# tusb_wiggler_-_b_conn.net
KiCad netlist of a schematic drawn in EAGLE
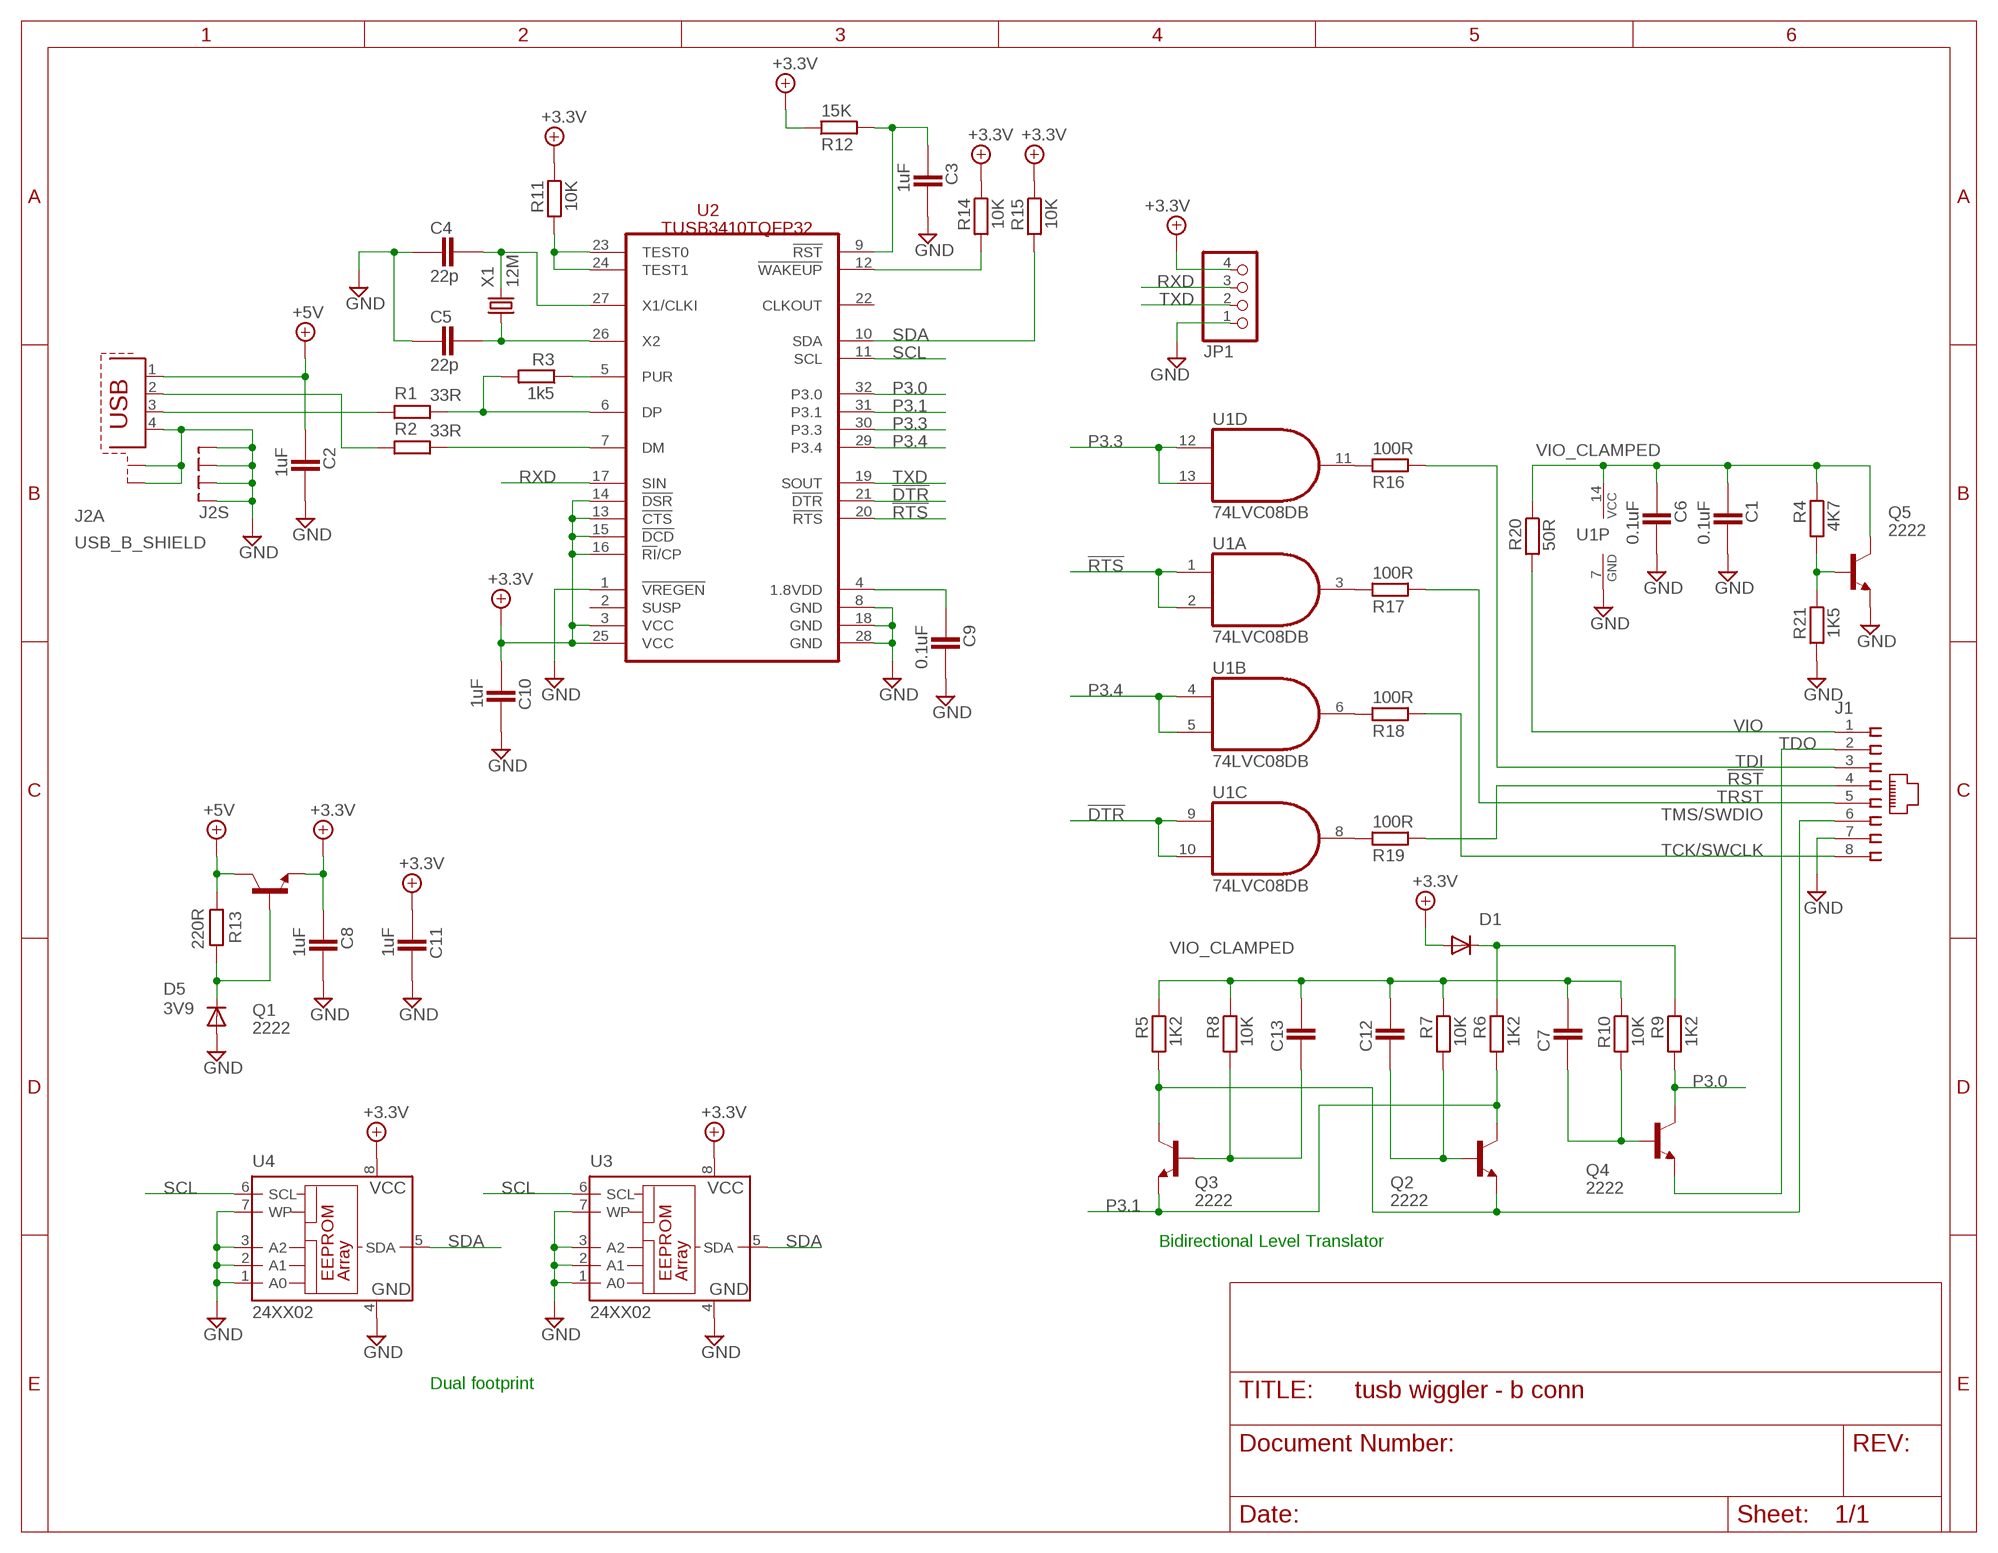
[diagram p0: schematic, sheet 1]

(export (version "E")
  (design (tool "Eeschema 10.0.6"))
  (components
    (comp (ref "C1")
      (value "0.1uF")
      (footprint "eagle-import:CAPC3215X168N")
      (libsource (lib "eagle-import") (part "CAPACITOR_1206"))
    )
    (comp (ref "C2")
      (value "1uF")
      (footprint "eagle-import:CAPC1608X92N")
      (libsource (lib "eagle-import") (part "CAPACITOR_0603"))
    )
    (comp (ref "C3")
      (value "1uF")
      (footprint "eagle-import:CAPC1608X92N")
      (libsource (lib "eagle-import") (part "CAPACITOR_0603"))
    )
    (comp (ref "C4")
      (value "22p")
      (footprint "eagle-import:CAP2012X70N")
      (libsource (lib "eagle-import") (part "CAPACITOR_0805N"))
    )
    (comp (ref "C5")
      (value "22p")
      (footprint "eagle-import:CAP2012X70N")
      (libsource (lib "eagle-import") (part "CAPACITOR_0805N"))
    )
    (comp (ref "C6")
      (value "0.1uF")
      (footprint "eagle-import:CAPC1608X92N")
      (libsource (lib "eagle-import") (part "CAPACITOR_0603"))
    )
    (comp (ref "C7")
      (value "CAPACITOR_0805N")
      (footprint "eagle-import:CAP2012X70N")
      (libsource (lib "eagle-import") (part "CAPACITOR_0805N"))
    )
    (comp (ref "C8")
      (value "1uF")
      (footprint "eagle-import:CAPC1608X92N")
      (libsource (lib "eagle-import") (part "CAPACITOR_0603"))
    )
    (comp (ref "C9")
      (value "0.1uF")
      (footprint "eagle-import:CAP2012X70N")
      (libsource (lib "eagle-import") (part "CAPACITOR_0805N"))
    )
    (comp (ref "C10")
      (value "1uF")
      (footprint "eagle-import:CAPC1608X92N")
      (libsource (lib "eagle-import") (part "CAPACITOR_0603"))
    )
    (comp (ref "C11")
      (value "1uF")
      (footprint "eagle-import:CAPC1608X92N")
      (libsource (lib "eagle-import") (part "CAPACITOR_0603"))
    )
    (comp (ref "C12")
      (value "CAPACITOR_0805N")
      (footprint "eagle-import:CAP2012X70N")
      (libsource (lib "eagle-import") (part "CAPACITOR_0805N"))
    )
    (comp (ref "C13")
      (value "CAPACITOR_0805N")
      (footprint "eagle-import:CAP2012X70N")
      (libsource (lib "eagle-import") (part "CAPACITOR_0805N"))
    )
    (comp (ref "D1")
      (value "DIODE-SOD110-W")
      (footprint "eagle-import:SOD110-W")
      (libsource (lib "eagle-import") (part "DIODE-SOD110-W"))
    )
    (comp (ref "D5")
      (value "3V9")
      (footprint "eagle-import:MELF-MLL41")
      (libsource (lib "eagle-import") (part "DIODE-MELF-MLL41"))
    )
    (comp (ref "J1")
      (value "520426-4")
      (footprint "eagle-import:520426-4")
      (libsource (lib "eagle-import") (part "520426-4"))
    )
    (comp (ref "J2")
      (value "USB_B_SHIELD")
      (footprint "eagle-import:PN61729-S")
      (libsource (lib "eagle-import") (part "USB_B_SHIELD"))
    )
    (comp (ref "JP1")
      (value "PINHD-1X4_2.54")
      (footprint "eagle-import:1X04")
      (libsource (lib "eagle-import") (part "PINHD-1X4_2.54"))
    )
    (comp (ref "Q1")
      (value "2222")
      (footprint "eagle-import:SOT95P280X135-3N")
      (libsource (lib "eagle-import") (part "NPN_SOT-23"))
    )
    (comp (ref "Q2")
      (value "2222")
      (footprint "eagle-import:SOT95P280X135-3N")
      (libsource (lib "eagle-import") (part "NPN_SOT-23"))
    )
    (comp (ref "Q3")
      (value "2222")
      (footprint "eagle-import:SOT95P280X135-3N")
      (libsource (lib "eagle-import") (part "NPN_SOT-23"))
    )
    (comp (ref "Q4")
      (value "2222")
      (footprint "eagle-import:SOT95P280X135-3N")
      (libsource (lib "eagle-import") (part "NPN_SOT-23"))
    )
    (comp (ref "Q5")
      (value "2222")
      (footprint "eagle-import:SOT95P280X135-3N")
      (libsource (lib "eagle-import") (part "NPN_SOT-23"))
    )
    (comp (ref "R1")
      (value "33R")
      (footprint "eagle-import:RESC1608X55N")
      (libsource (lib "eagle-import") (part "RESISTOR_0603"))
    )
    (comp (ref "R2")
      (value "33R")
      (footprint "eagle-import:RESC1608X55N")
      (libsource (lib "eagle-import") (part "RESISTOR_0603"))
    )
    (comp (ref "R3")
      (value "1k5")
      (footprint "eagle-import:RESC1608X55N")
      (libsource (lib "eagle-import") (part "RESISTOR_0603"))
    )
    (comp (ref "R4")
      (value "4K7")
      (footprint "eagle-import:RESC1608X55N")
      (libsource (lib "eagle-import") (part "RESISTOR_0603"))
    )
    (comp (ref "R5")
      (value "1K2")
      (footprint "eagle-import:RESC1608X55N")
      (libsource (lib "eagle-import") (part "RESISTOR_0603"))
    )
    (comp (ref "R6")
      (value "1K2")
      (footprint "eagle-import:RESC1608X55N")
      (libsource (lib "eagle-import") (part "RESISTOR_0603"))
    )
    (comp (ref "R7")
      (value "10K")
      (footprint "eagle-import:RESC1608X55N")
      (libsource (lib "eagle-import") (part "RESISTOR_0603"))
    )
    (comp (ref "R8")
      (value "10K")
      (footprint "eagle-import:RESC1608X55N")
      (libsource (lib "eagle-import") (part "RESISTOR_0603"))
    )
    (comp (ref "R9")
      (value "1K2")
      (footprint "eagle-import:RESC1608X55N")
      (libsource (lib "eagle-import") (part "RESISTOR_0603"))
    )
    (comp (ref "R10")
      (value "10K")
      (footprint "eagle-import:RESC1608X55N")
      (libsource (lib "eagle-import") (part "RESISTOR_0603"))
    )
    (comp (ref "R11")
      (value "10K")
      (footprint "eagle-import:RESC1608X55N")
      (libsource (lib "eagle-import") (part "RESISTOR_0603"))
    )
    (comp (ref "R12")
      (value "15K")
      (footprint "eagle-import:RESC1608X55N")
      (libsource (lib "eagle-import") (part "RESISTOR_0603"))
    )
    (comp (ref "R13")
      (value "220R")
      (footprint "eagle-import:RESC1608X55N")
      (libsource (lib "eagle-import") (part "RESISTOR_0603"))
    )
    (comp (ref "R14")
      (value "10K")
      (footprint "eagle-import:RESC1608X55N")
      (libsource (lib "eagle-import") (part "RESISTOR_0603"))
    )
    (comp (ref "R15")
      (value "10K")
      (footprint "eagle-import:RESC1608X55N")
      (libsource (lib "eagle-import") (part "RESISTOR_0603"))
    )
    (comp (ref "R16")
      (value "100R")
      (footprint "eagle-import:RESC3115X70N")
      (libsource (lib "eagle-import") (part "RESISTOR_1206"))
    )
    (comp (ref "R17")
      (value "100R")
      (footprint "eagle-import:RESC3115X70N")
      (libsource (lib "eagle-import") (part "RESISTOR_1206"))
    )
    (comp (ref "R18")
      (value "100R")
      (footprint "eagle-import:RESC3115X70N")
      (libsource (lib "eagle-import") (part "RESISTOR_1206"))
    )
    (comp (ref "R19")
      (value "100R")
      (footprint "eagle-import:RESC3115X70N")
      (libsource (lib "eagle-import") (part "RESISTOR_1206"))
    )
    (comp (ref "R20")
      (value "50R")
      (footprint "eagle-import:RESC1608X55N")
      (libsource (lib "eagle-import") (part "RESISTOR_0603"))
    )
    (comp (ref "R21")
      (value "1K5")
      (footprint "eagle-import:RESC1608X55N")
      (libsource (lib "eagle-import") (part "RESISTOR_0603"))
    )
    (comp (ref "U1")
      (value "74LVC08DB")
      (footprint "eagle-import:TSSOP14")
      (libsource (lib "eagle-import") (part "7408DB"))
    )
    (comp (ref "U2")
      (value "TUSB3410TQFP32")
      (footprint "eagle-import:TQFP32-08")
      (libsource (lib "eagle-import") (part "TUSB3410TQFP32"))
    )
    (comp (ref "U3")
      (value "24XX02")
      (footprint "eagle-import:TSSOP8")
      (libsource (lib "eagle-import") (part "24STAA64"))
    )
    (comp (ref "U4")
      (value "24XX02")
      (footprint "eagle-import:SO-08")
      (libsource (lib "eagle-import") (part "24SNAA64"))
    )
    (comp (ref "X1")
      (value "12M")
      (footprint "eagle-import:HC49UP")
      (libsource (lib "eagle-import") (part "CRYSTALHC49UP"))
    )
  )
  (nets
    (net (code "1") (name "+3.3V") (class "Default")
      (node (ref "C10") (pin "1") (pinfunction "1_1") (pintype "passive"))
      (node (ref "C11") (pin "1") (pinfunction "1_1") (pintype "passive"))
      (node (ref "C8") (pin "1") (pinfunction "1_1") (pintype "passive"))
      (node (ref "D1") (pin "A") (pinfunction "A_A") (pintype "passive"))
      (node (ref "JP1") (pin "4") (pinfunction "4_4") (pintype "passive"))
      (node (ref "Q1") (pin "2") (pinfunction "E_2") (pintype "passive"))
      (node (ref "R11") (pin "1") (pinfunction "1_1") (pintype "passive"))
      (node (ref "R12") (pin "1") (pinfunction "1_1") (pintype "passive"))
      (node (ref "R14") (pin "1") (pinfunction "1_1") (pintype "passive"))
      (node (ref "R15") (pin "1") (pinfunction "1_1") (pintype "passive"))
      (node (ref "U2") (pin "13") (pinfunction "~{CTS}_13") (pintype "bidirectional"))
      (node (ref "U2") (pin "14") (pinfunction "~{DSR}_14") (pintype "bidirectional"))
      (node (ref "U2") (pin "15") (pinfunction "~{DCD}_15") (pintype "bidirectional"))
      (node (ref "U2") (pin "16") (pinfunction "~{RI}/CP_16") (pintype "bidirectional"))
      (node (ref "U2") (pin "25") (pinfunction "VCC_25") (pintype "power_in"))
      (node (ref "U2") (pin "3") (pinfunction "VCC_3") (pintype "power_in"))
      (node (ref "U3") (pin "8") (pinfunction "VCC_8") (pintype "power_in"))
      (node (ref "U4") (pin "8") (pinfunction "VCC_8") (pintype "power_in"))
    )
    (net (code "2") (name "+5V") (class "Default")
      (node (ref "C2") (pin "1") (pinfunction "1_1") (pintype "passive"))
      (node (ref "J2") (pin "1") (pinfunction "1_1") (pintype "passive"))
      (node (ref "Q1") (pin "3") (pinfunction "C_3") (pintype "passive"))
      (node (ref "R13") (pin "1") (pinfunction "1_1") (pintype "passive"))
    )
    (net (code "3") (name "/P3.0") (class "Default")
      (node (ref "Q4") (pin "3") (pinfunction "C_3") (pintype "passive"))
      (node (ref "R9") (pin "2") (pinfunction "2_2") (pintype "passive"))
      (node (ref "U2") (pin "32") (pinfunction "P3.0_32") (pintype "bidirectional"))
    )
    (net (code "4") (name "/P3.1") (class "Default")
      (node (ref "Q2") (pin "3") (pinfunction "C_3") (pintype "passive"))
      (node (ref "Q3") (pin "2") (pinfunction "E_2") (pintype "passive"))
      (node (ref "R6") (pin "2") (pinfunction "2_2") (pintype "passive"))
      (node (ref "U2") (pin "31") (pinfunction "P3.1_31") (pintype "bidirectional"))
    )
    (net (code "5") (name "/P3.3") (class "Default")
      (node (ref "U1") (pin "12") (pinfunction "I0_12") (pintype "input"))
      (node (ref "U1") (pin "13") (pinfunction "I1_13") (pintype "input"))
      (node (ref "U2") (pin "30") (pinfunction "P3.3_30") (pintype "bidirectional"))
    )
    (net (code "6") (name "/P3.4") (class "Default")
      (node (ref "U1") (pin "4") (pinfunction "I0_4") (pintype "input"))
      (node (ref "U1") (pin "5") (pinfunction "I1_5") (pintype "input"))
      (node (ref "U2") (pin "29") (pinfunction "P3.4_29") (pintype "bidirectional"))
    )
    (net (code "7") (name "/RXD") (class "Default")
      (node (ref "JP1") (pin "3") (pinfunction "3_3") (pintype "passive"))
      (node (ref "U2") (pin "17") (pinfunction "SIN_17") (pintype "bidirectional"))
    )
    (net (code "8") (name "/SCL") (class "Default")
      (node (ref "U2") (pin "11") (pinfunction "SCL_11") (pintype "bidirectional"))
      (node (ref "U3") (pin "6") (pinfunction "SCL_6") (pintype "input"))
      (node (ref "U4") (pin "6") (pinfunction "SCL_6") (pintype "input"))
    )
    (net (code "9") (name "/SDA") (class "Default")
      (node (ref "R15") (pin "2") (pinfunction "2_2") (pintype "passive"))
      (node (ref "U2") (pin "10") (pinfunction "SDA_10") (pintype "bidirectional"))
      (node (ref "U3") (pin "5") (pinfunction "SDA_5") (pintype "bidirectional"))
      (node (ref "U4") (pin "5") (pinfunction "SDA_5") (pintype "bidirectional"))
    )
    (net (code "10") (name "/TCK{slash}SWCLK") (class "Default")
      (node (ref "J1") (pin "8") (pinfunction "8_8") (pintype "passive"))
      (node (ref "R18") (pin "2") (pinfunction "2_2") (pintype "passive"))
    )
    (net (code "11") (name "/TDI") (class "Default")
      (node (ref "J1") (pin "3") (pinfunction "3_3") (pintype "passive"))
      (node (ref "R16") (pin "2") (pinfunction "2_2") (pintype "passive"))
    )
    (net (code "12") (name "/TDO") (class "Default")
      (node (ref "J1") (pin "2") (pinfunction "2_2") (pintype "passive"))
      (node (ref "Q4") (pin "2") (pinfunction "E_2") (pintype "passive"))
    )
    (net (code "13") (name "/TMS{slash}SWDIO") (class "Default")
      (node (ref "J1") (pin "6") (pinfunction "6_6") (pintype "passive"))
      (node (ref "Q2") (pin "2") (pinfunction "E_2") (pintype "passive"))
      (node (ref "Q3") (pin "3") (pinfunction "C_3") (pintype "passive"))
      (node (ref "R5") (pin "2") (pinfunction "2_2") (pintype "passive"))
    )
    (net (code "14") (name "/TRST") (class "Default")
      (node (ref "J1") (pin "5") (pinfunction "5_5") (pintype "passive"))
      (node (ref "R17") (pin "2") (pinfunction "2_2") (pintype "passive"))
    )
    (net (code "15") (name "/TXD") (class "Default")
      (node (ref "JP1") (pin "2") (pinfunction "2_2") (pintype "passive"))
      (node (ref "U2") (pin "19") (pinfunction "SOUT_19") (pintype "bidirectional"))
    )
    (net (code "16") (name "/VIO") (class "Default")
      (node (ref "J1") (pin "1") (pinfunction "1_1") (pintype "passive"))
      (node (ref "R20") (pin "2") (pinfunction "2_2") (pintype "passive"))
    )
    (net (code "17") (name "/VIO_CLAMPED") (class "Default")
      (node (ref "C1") (pin "1") (pinfunction "1_1") (pintype "passive"))
      (node (ref "C12") (pin "2") (pinfunction "2_2") (pintype "passive"))
      (node (ref "C13") (pin "2") (pinfunction "2_2") (pintype "passive"))
      (node (ref "C6") (pin "1") (pinfunction "1_1") (pintype "passive"))
      (node (ref "C7") (pin "2") (pinfunction "2_2") (pintype "passive"))
      (node (ref "Q5") (pin "3") (pinfunction "C_3") (pintype "passive"))
      (node (ref "R10") (pin "1") (pinfunction "1_1") (pintype "passive"))
      (node (ref "R20") (pin "1") (pinfunction "1_1") (pintype "passive"))
      (node (ref "R4") (pin "1") (pinfunction "1_1") (pintype "passive"))
      (node (ref "R5") (pin "1") (pinfunction "1_1") (pintype "passive"))
      (node (ref "R7") (pin "1") (pinfunction "1_1") (pintype "passive"))
      (node (ref "R8") (pin "1") (pinfunction "1_1") (pintype "passive"))
      (node (ref "U1") (pin "14") (pinfunction "VCC_14") (pintype "input"))
    )
    (net (code "18") (name "/~{DTR}") (class "Default")
      (node (ref "U1") (pin "10") (pinfunction "I1_10") (pintype "input"))
      (node (ref "U1") (pin "9") (pinfunction "I0_9") (pintype "input"))
      (node (ref "U2") (pin "21") (pinfunction "~{DTR}_21") (pintype "bidirectional"))
    )
    (net (code "19") (name "/~{RST}") (class "Default")
      (node (ref "J1") (pin "4") (pinfunction "4_4") (pintype "passive"))
      (node (ref "R19") (pin "2") (pinfunction "2_2") (pintype "passive"))
    )
    (net (code "20") (name "/~{RTS}") (class "Default")
      (node (ref "U1") (pin "1") (pinfunction "I0_1") (pintype "input"))
      (node (ref "U1") (pin "2") (pinfunction "I1_2") (pintype "input"))
      (node (ref "U2") (pin "20") (pinfunction "~{RTS}_20") (pintype "bidirectional"))
    )
    (net (code "21") (name "GND") (class "Default")
      (node (ref "C1") (pin "2") (pinfunction "2_2") (pintype "passive"))
      (node (ref "C10") (pin "2") (pinfunction "2_2") (pintype "passive"))
      (node (ref "C11") (pin "2") (pinfunction "2_2") (pintype "passive"))
      (node (ref "C2") (pin "2") (pinfunction "2_2") (pintype "passive"))
      (node (ref "C3") (pin "2") (pinfunction "2_2") (pintype "passive"))
      (node (ref "C4") (pin "1") (pinfunction "1_1") (pintype "passive"))
      (node (ref "C5") (pin "1") (pinfunction "1_1") (pintype "passive"))
      (node (ref "C6") (pin "2") (pinfunction "2_2") (pintype "passive"))
      (node (ref "C8") (pin "2") (pinfunction "2_2") (pintype "passive"))
      (node (ref "C9") (pin "2") (pinfunction "2_2") (pintype "passive"))
      (node (ref "D5") (pin "A") (pinfunction "A_A") (pintype "passive"))
      (node (ref "J1") (pin "7") (pinfunction "7_7") (pintype "passive"))
      (node (ref "J2") (pin "4") (pinfunction "4_4") (pintype "passive"))
      (node (ref "J2") (pin "G1") (pinfunction "S1_G1") (pintype "passive"))
      (node (ref "J2") (pin "G2") (pinfunction "S1_G2") (pintype "passive"))
      (node (ref "J2") (pin "G3") (pinfunction "S2_G3") (pintype "passive"))
      (node (ref "J2") (pin "G4") (pinfunction "S2_G4") (pintype "passive"))
      (node (ref "J2") (pin "G5") (pinfunction "S3_G5") (pintype "passive"))
      (node (ref "J2") (pin "G6") (pinfunction "S4_G6") (pintype "passive"))
      (node (ref "JP1") (pin "1") (pinfunction "1_1") (pintype "passive"))
      (node (ref "Q5") (pin "2") (pinfunction "E_2") (pintype "passive"))
      (node (ref "R21") (pin "2") (pinfunction "2_2") (pintype "passive"))
      (node (ref "U1") (pin "7") (pinfunction "GND_7") (pintype "input"))
      (node (ref "U2") (pin "1") (pinfunction "~{VREGEN}_1") (pintype "bidirectional"))
      (node (ref "U2") (pin "18") (pinfunction "GND_18") (pintype "power_in"))
      (node (ref "U2") (pin "28") (pinfunction "GND_28") (pintype "power_in"))
      (node (ref "U2") (pin "8") (pinfunction "GND_8") (pintype "bidirectional"))
      (node (ref "U3") (pin "1") (pinfunction "A0_1") (pintype "input"))
      (node (ref "U3") (pin "2") (pinfunction "A1_2") (pintype "input"))
      (node (ref "U3") (pin "3") (pinfunction "A2_3") (pintype "input"))
      (node (ref "U3") (pin "4") (pinfunction "GND_4") (pintype "power_in"))
      (node (ref "U3") (pin "7") (pinfunction "WP_7") (pintype "input"))
      (node (ref "U4") (pin "1") (pinfunction "A0_1") (pintype "input"))
      (node (ref "U4") (pin "2") (pinfunction "A1_2") (pintype "input"))
      (node (ref "U4") (pin "3") (pinfunction "A2_3") (pintype "input"))
      (node (ref "U4") (pin "4") (pinfunction "GND_4") (pintype "power_in"))
      (node (ref "U4") (pin "7") (pinfunction "WP_7") (pintype "input"))
    )
    (net (code "22") (name "Net-(D1-PadC)") (class "Default")
      (node (ref "D1") (pin "C") (pinfunction "C_C") (pintype "passive"))
      (node (ref "R6") (pin "1") (pinfunction "1_1") (pintype "passive"))
      (node (ref "R9") (pin "1") (pinfunction "1_1") (pintype "passive"))
    )
    (net (code "23") (name "Net-(J2-Pad2)") (class "Default")
      (node (ref "J2") (pin "2") (pinfunction "2_2") (pintype "passive"))
      (node (ref "R2") (pin "1") (pinfunction "1_1") (pintype "passive"))
    )
    (net (code "24") (name "Net-(J2-Pad3)") (class "Default")
      (node (ref "J2") (pin "3") (pinfunction "3_3") (pintype "passive"))
      (node (ref "R1") (pin "1") (pinfunction "1_1") (pintype "passive"))
    )
    (net (code "25") (name "Net-(Q1-B)") (class "Default")
      (node (ref "D5") (pin "C") (pinfunction "C_C") (pintype "passive"))
      (node (ref "Q1") (pin "1") (pinfunction "B_1") (pintype "passive"))
      (node (ref "R13") (pin "2") (pinfunction "2_2") (pintype "passive"))
    )
    (net (code "26") (name "Net-(Q2-B)") (class "Default")
      (node (ref "C12") (pin "1") (pinfunction "1_1") (pintype "passive"))
      (node (ref "Q2") (pin "1") (pinfunction "B_1") (pintype "passive"))
      (node (ref "R7") (pin "2") (pinfunction "2_2") (pintype "passive"))
    )
    (net (code "27") (name "Net-(Q3-B)") (class "Default")
      (node (ref "C13") (pin "1") (pinfunction "1_1") (pintype "passive"))
      (node (ref "Q3") (pin "1") (pinfunction "B_1") (pintype "passive"))
      (node (ref "R8") (pin "2") (pinfunction "2_2") (pintype "passive"))
    )
    (net (code "28") (name "Net-(Q4-B)") (class "Default")
      (node (ref "C7") (pin "1") (pinfunction "1_1") (pintype "passive"))
      (node (ref "Q4") (pin "1") (pinfunction "B_1") (pintype "passive"))
      (node (ref "R10") (pin "2") (pinfunction "2_2") (pintype "passive"))
    )
    (net (code "29") (name "Net-(Q5-B)") (class "Default")
      (node (ref "Q5") (pin "1") (pinfunction "B_1") (pintype "passive"))
      (node (ref "R21") (pin "1") (pinfunction "1_1") (pintype "passive"))
      (node (ref "R4") (pin "2") (pinfunction "2_2") (pintype "passive"))
    )
    (net (code "30") (name "Net-(U1A-O)") (class "Default")
      (node (ref "R17") (pin "1") (pinfunction "1_1") (pintype "passive"))
      (node (ref "U1") (pin "3") (pinfunction "O_3") (pintype "output"))
    )
    (net (code "31") (name "Net-(U1B-O)") (class "Default")
      (node (ref "R18") (pin "1") (pinfunction "1_1") (pintype "passive"))
      (node (ref "U1") (pin "6") (pinfunction "O_6") (pintype "output"))
    )
    (net (code "32") (name "Net-(U1C-O)") (class "Default")
      (node (ref "R19") (pin "1") (pinfunction "1_1") (pintype "passive"))
      (node (ref "U1") (pin "8") (pinfunction "O_8") (pintype "output"))
    )
    (net (code "33") (name "Net-(U1D-O)") (class "Default")
      (node (ref "R16") (pin "1") (pinfunction "1_1") (pintype "passive"))
      (node (ref "U1") (pin "11") (pinfunction "O_11") (pintype "output"))
    )
    (net (code "34") (name "Net-(U2-1.8VDD)") (class "Default")
      (node (ref "C9") (pin "1") (pinfunction "1_1") (pintype "passive"))
      (node (ref "U2") (pin "4") (pinfunction "1.8VDD_4") (pintype "power_in"))
    )
    (net (code "35") (name "Net-(U2-DM)") (class "Default")
      (node (ref "R2") (pin "2") (pinfunction "2_2") (pintype "passive"))
      (node (ref "U2") (pin "7") (pinfunction "DM_7") (pintype "bidirectional"))
    )
    (net (code "36") (name "Net-(U2-DP)") (class "Default")
      (node (ref "R1") (pin "2") (pinfunction "2_2") (pintype "passive"))
      (node (ref "R3") (pin "2") (pinfunction "2_2") (pintype "passive"))
      (node (ref "U2") (pin "6") (pinfunction "DP_6") (pintype "bidirectional"))
    )
    (net (code "37") (name "Net-(U2-PUR)") (class "Default")
      (node (ref "R3") (pin "1") (pinfunction "1_1") (pintype "passive"))
      (node (ref "U2") (pin "5") (pinfunction "PUR_5") (pintype "bidirectional"))
    )
    (net (code "38") (name "Net-(U2-TEST0)") (class "Default")
      (node (ref "R11") (pin "2") (pinfunction "2_2") (pintype "passive"))
      (node (ref "U2") (pin "23") (pinfunction "TEST0_23") (pintype "bidirectional"))
      (node (ref "U2") (pin "24") (pinfunction "TEST1_24") (pintype "bidirectional"))
    )
    (net (code "39") (name "Net-(U2-X1{slash}CLKI)") (class "Default")
      (node (ref "C4") (pin "2") (pinfunction "2_2") (pintype "passive"))
      (node (ref "U2") (pin "27") (pinfunction "X1/CLKI_27") (pintype "bidirectional"))
      (node (ref "X1") (pin "2") (pinfunction "2_2") (pintype "passive"))
    )
    (net (code "40") (name "Net-(U2-X2)") (class "Default")
      (node (ref "C5") (pin "2") (pinfunction "2_2") (pintype "passive"))
      (node (ref "U2") (pin "26") (pinfunction "X2_26") (pintype "bidirectional"))
      (node (ref "X1") (pin "1") (pinfunction "1_1") (pintype "passive"))
    )
    (net (code "41") (name "Net-(U2-~{RST})") (class "Default")
      (node (ref "C3") (pin "1") (pinfunction "1_1") (pintype "passive"))
      (node (ref "R12") (pin "2") (pinfunction "2_2") (pintype "passive"))
      (node (ref "U2") (pin "9") (pinfunction "~{RST}_9") (pintype "bidirectional"))
    )
    (net (code "42") (name "Net-(U2-~{WAKEUP})") (class "Default")
      (node (ref "R14") (pin "2") (pinfunction "2_2") (pintype "passive"))
      (node (ref "U2") (pin "12") (pinfunction "~{WAKEUP}_12") (pintype "bidirectional"))
    )
    (net (code "43") (name "unconnected-(U2-CLKOUT-Pad22)") (class "Default")
      (node (ref "U2") (pin "22") (pinfunction "CLKOUT_22") (pintype "bidirectional"))
    )
    (net (code "44") (name "unconnected-(U2-SUSP-Pad2)") (class "Default")
      (node (ref "U2") (pin "2") (pinfunction "SUSP_2") (pintype "bidirectional"))
    )
  )
)
